# AudioAmplifier.net
KiCad netlist of a schematic drawn in Altium Designer
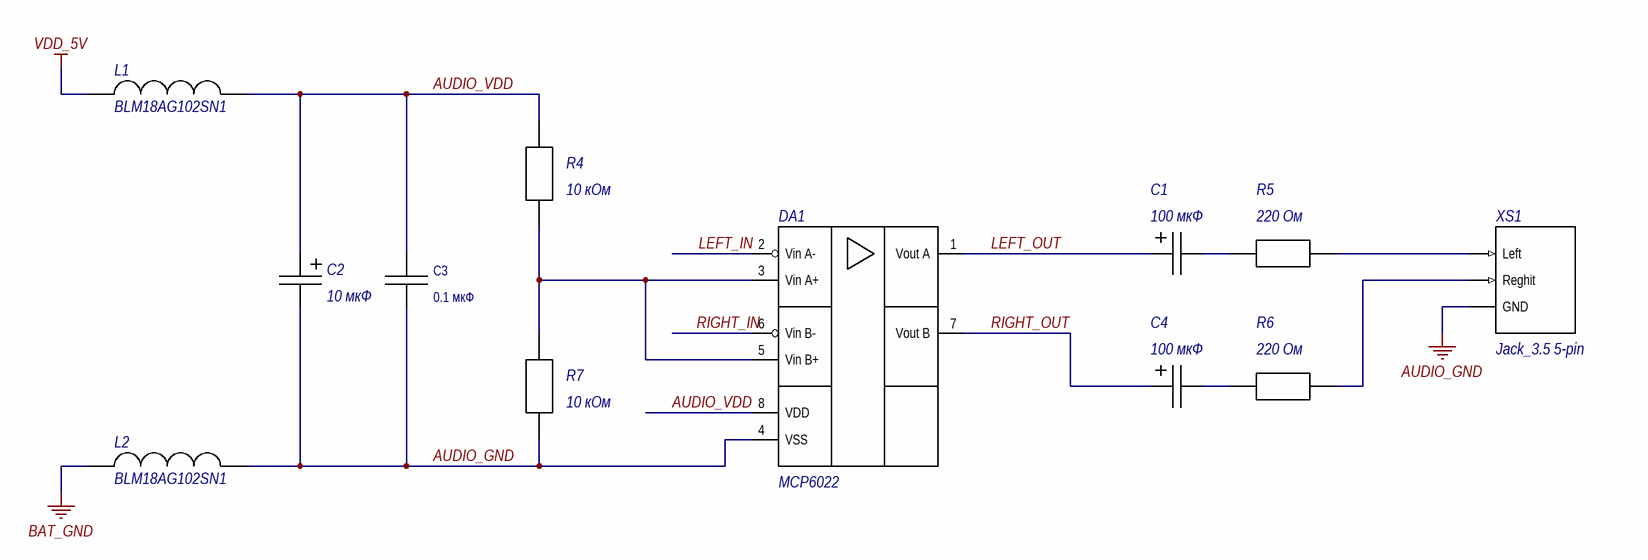
[diagram p0: AudioAmplifier.SchDoc]

(export (version "E")
  (design (tool "Eeschema 10.0.6"))
  (components
    (comp (ref "C1")
      (value "100 мкФ")
      (footprint "C TAN_C")
      (description "SMD Tantalium Capacitor C")
      (libsource (lib "my_lib") (part "CAP TAN_C"))
    )
    (comp (ref "C2")
      (value "10 мкФ")
      (footprint "C TAN_A")
      (description "SMD Tantalium Capacitor A")
      (libsource (lib "my_lib") (part "CAP TAN_A"))
    )
    (comp (ref "C3")
      (value "0.1 мкФ")
      (footprint "C 1206")
      (description "SMD Capacitor 1206")
      (fields
        (field (name "TOLERANCE") "/Укажите допуск в процентах/")
        (field (name "MANUFACTURER") "/Укажите компанию-производителя/")
      )
      (libsource (lib "my_lib") (part "CAP 1206"))
    )
    (comp (ref "C4")
      (value "100 мкФ")
      (footprint "C TAN_C")
      (description "SMD Tantalium Capacitor C")
      (libsource (lib "my_lib") (part "CAP TAN_C"))
    )
    (comp (ref "DA1") (value "MCP6022") (footprint "SOIC-8") (libsource (lib "my_lib") (part "MCP6022")))
    (comp (ref "L1")
      (value "BLM18AG102SN1")
      (footprint "FB 0603")
      (libsource (lib "my_lib") (part "BLM18AG102SN1"))
    )
    (comp (ref "L2")
      (value "BLM18AG102SN1")
      (footprint "FB 0603")
      (libsource (lib "my_lib") (part "BLM18AG102SN1"))
    )
    (comp (ref "R4") (value "10 кОм") (footprint "RES 0805") (libsource (lib "my_lib") (part "RES 0805")))
    (comp (ref "R5") (value "220 Ом") (footprint "RES 0805") (libsource (lib "my_lib") (part "RES 0805")))
    (comp (ref "R6") (value "220 Ом") (footprint "RES 0805") (libsource (lib "my_lib") (part "RES 0805")))
    (comp (ref "R7") (value "10 кОм") (footprint "RES 0805") (libsource (lib "my_lib") (part "RES 0805")))
    (comp (ref "XS1")
      (value "Jack_3.5 5-pin")
      (footprint "JACK 3.5 DIP")
      (libsource (lib "my_lib") (part "Jack_3.5 5-pin"))
    )
  )
  (nets
    (net (code "1") (name "/AUDIO_VDD") (class "Default")
      (node (ref "C2") (pin "1") (pinfunction "1_1") (pintype "passive"))
      (node (ref "C3") (pin "1") (pinfunction "1_1") (pintype "passive"))
      (node (ref "DA1") (pin "8") (pinfunction "VDD_8") (pintype "power_in"))
      (node (ref "L1") (pin "2") (pinfunction "2_2") (pintype "passive"))
      (node (ref "R4") (pin "2") (pinfunction "2_2") (pintype "passive"))
    )
    (net (code "2") (name "/LEFT_IN") (class "Default")
      (node (ref "DA1") (pin "2") (pinfunction "Vin_A-_2") (pintype "passive"))
    )
    (net (code "3") (name "/LEFT_OUT") (class "Default")
      (node (ref "C1") (pin "1") (pinfunction "1_1") (pintype "passive"))
      (node (ref "DA1") (pin "1") (pinfunction "Vout_A_1") (pintype "passive"))
    )
    (net (code "4") (name "/RIGHT_IN") (class "Default")
      (node (ref "DA1") (pin "6") (pinfunction "Vin_B-_6") (pintype "passive"))
    )
    (net (code "5") (name "/RIGHT_OUT") (class "Default")
      (node (ref "C4") (pin "1") (pinfunction "1_1") (pintype "passive"))
      (node (ref "DA1") (pin "7") (pinfunction "Vout_B_7") (pintype "passive"))
    )
    (net (code "6") (name "AUDIO_GND") (class "Default")
      (node (ref "C2") (pin "2") (pinfunction "2_2") (pintype "passive"))
      (node (ref "C3") (pin "2") (pinfunction "2_2") (pintype "passive"))
      (node (ref "DA1") (pin "4") (pinfunction "VSS_4") (pintype "power_in"))
      (node (ref "L2") (pin "2") (pinfunction "2_2") (pintype "passive"))
      (node (ref "R7") (pin "1") (pinfunction "1_1") (pintype "passive"))
      (node (ref "XS1") (pin "G") (pinfunction "GND_G") (pintype "power_in"))
    )
    (net (code "7") (name "BAT_GND") (class "Default")
      (node (ref "L2") (pin "1") (pinfunction "1_1") (pintype "passive"))
    )
    (net (code "8") (name "Net-(C1-Pad2)") (class "Default")
      (node (ref "C1") (pin "2") (pinfunction "2_2") (pintype "passive"))
      (node (ref "R5") (pin "1") (pinfunction "1_1") (pintype "passive"))
    )
    (net (code "9") (name "Net-(C4-Pad2)") (class "Default")
      (node (ref "C4") (pin "2") (pinfunction "2_2") (pintype "passive"))
      (node (ref "R6") (pin "1") (pinfunction "1_1") (pintype "passive"))
    )
    (net (code "10") (name "Net-(DA1-Vin_A+)") (class "Default")
      (node (ref "DA1") (pin "3") (pinfunction "Vin_A+_3") (pintype "passive"))
      (node (ref "DA1") (pin "5") (pinfunction "Vin_B+_5") (pintype "passive"))
      (node (ref "R4") (pin "1") (pinfunction "1_1") (pintype "passive"))
      (node (ref "R7") (pin "2") (pinfunction "2_2") (pintype "passive"))
    )
    (net (code "11") (name "Net-(XS1-Left)") (class "Default")
      (node (ref "R5") (pin "2") (pinfunction "2_2") (pintype "passive"))
      (node (ref "XS1") (pin "L") (pinfunction "Left_L") (pintype "input"))
    )
    (net (code "12") (name "Net-(XS1-Reghit)") (class "Default")
      (node (ref "R6") (pin "2") (pinfunction "2_2") (pintype "passive"))
      (node (ref "XS1") (pin "R") (pinfunction "Reghit_R") (pintype "input"))
    )
    (net (code "13") (name "VDD_5V") (class "Default")
      (node (ref "L1") (pin "1") (pinfunction "1_1") (pintype "passive"))
    )
  )
)
